# Steering_Wheel_Carrier_Board_Mezzanine.net
KiCad netlist of a schematic drawn in Altium Designer
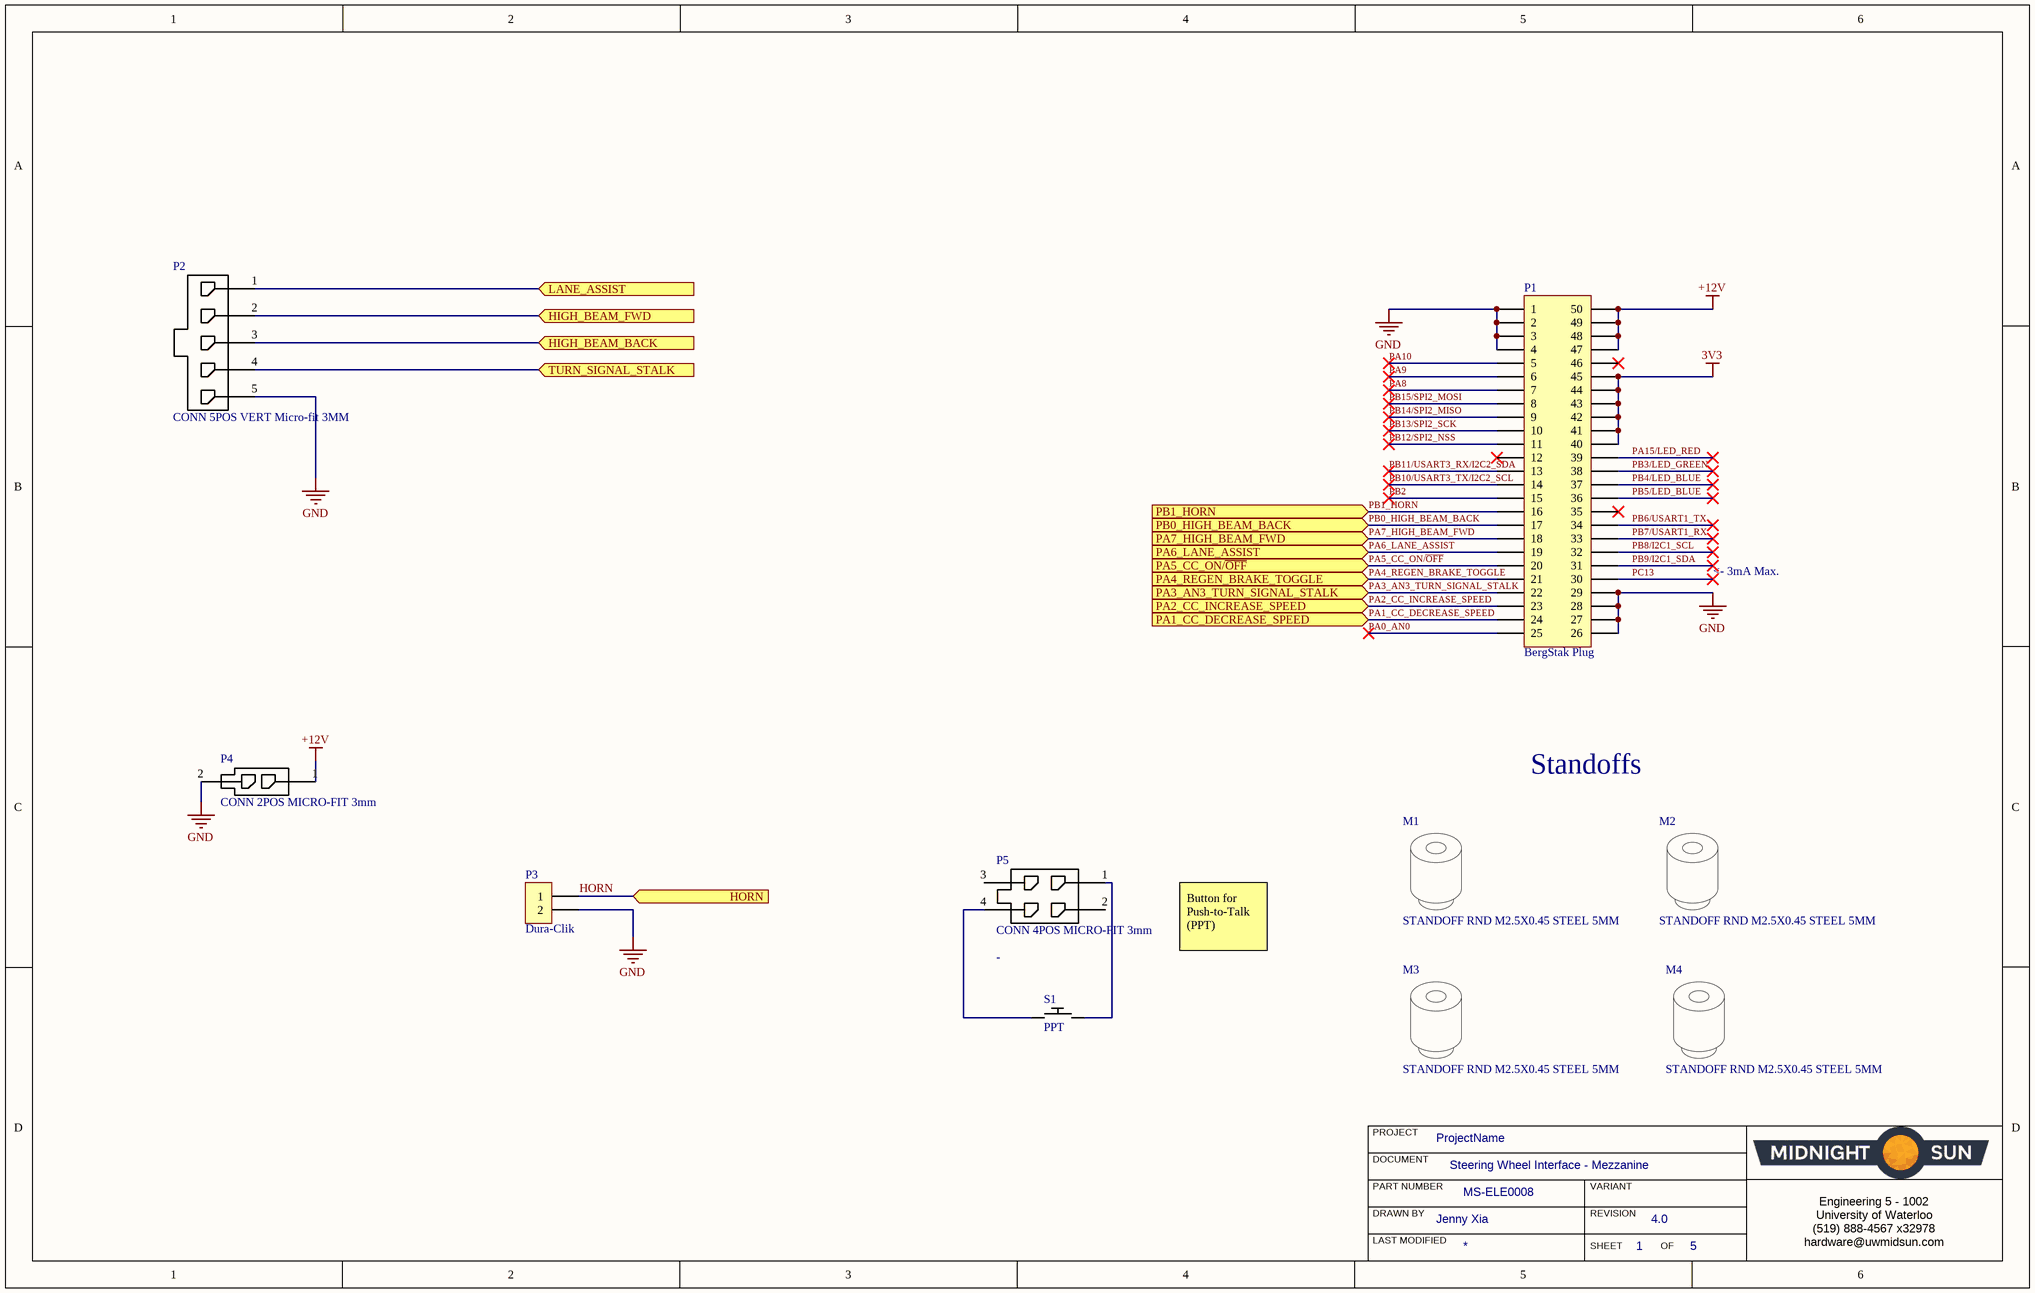
[diagram p0: Steering Wheel Carrier Board Mezzanine.SchDoc]

(export (version "E")
  (design (tool "Eeschema 10.0.6"))
  (components
    (comp (ref "M1")
      (value "STANDOFF RND M2.5X0.45 STEEL 5MM")
      (footprint "M2.5 Standoff")
      (fields
        (field (name "MANUFACTURER") "Wurth Electronics")
        (field (name "MANUFACTURER PART NUMBER") "9774050151R")
        (field (name "SOURCE") "Schematic Diagrams.SchLib")
      )
      (libsource (lib "University of Waterloo - Solar Car Team") (part "STANDOFF RND M2.5X0.45 STEEL 5MM"))
    )
    (comp (ref "M2")
      (value "STANDOFF RND M2.5X0.45 STEEL 5MM")
      (footprint "M2.5 Standoff")
      (fields
        (field (name "MANUFACTURER") "Wurth Electronics")
        (field (name "MANUFACTURER PART NUMBER") "9774050151R")
        (field (name "SOURCE") "Schematic Diagrams.SchLib")
      )
      (libsource (lib "University of Waterloo - Solar Car Team") (part "STANDOFF RND M2.5X0.45 STEEL 5MM"))
    )
    (comp (ref "M3")
      (value "STANDOFF RND M2.5X0.45 STEEL 5MM")
      (footprint "M2.5 Standoff")
      (fields
        (field (name "MANUFACTURER") "Wurth Electronics")
        (field (name "MANUFACTURER PART NUMBER") "9774050151R")
        (field (name "SOURCE") "Schematic Diagrams.SchLib")
      )
      (libsource (lib "University of Waterloo - Solar Car Team") (part "STANDOFF RND M2.5X0.45 STEEL 5MM"))
    )
    (comp (ref "M4")
      (value "STANDOFF RND M2.5X0.45 STEEL 5MM")
      (footprint "M2.5 Standoff")
      (fields
        (field (name "MANUFACTURER") "Wurth Electronics")
        (field (name "MANUFACTURER PART NUMBER") "9774050151R")
        (field (name "SOURCE") "Schematic Diagrams.SchLib")
      )
      (libsource (lib "University of Waterloo - Solar Car Team") (part "STANDOFF RND M2.5X0.45 STEEL 5MM"))
    )
    (comp (ref "P1")
      (value "CONN 50POS Bergstak Plug 0.02\"")
      (footprint "CONN, Bergstak 50 Pos Plug")
      (description "50 Position Connector Plug, Outer Shroud Contacts Surface Mount Gold")
      (fields (field (name "SERIES") "BergStak Plug"))
      (libsource (lib "Schematic Diagrams") (part "CONN 50POS Bergstak Plug 0.02{dblquote}"))
    )
    (comp (ref "P2")
      (value "CONN 5POS VERT Micro-fit 3MM")
      (footprint "CONN, 5POS MICRO-FIT 3mm")
      (description "Conn Power HDR 5 POS 3mm Solder ST Thru-Hole 5 Terminal 1 Port Micro-Fit 3.0™ Tray")
      (fields (field (name "MANUFACTURER PART NUMBER") "0436500516") (field (name "MANUFACTURER") "Molex"))
      (libsource (lib "University of Waterloo - Solar Car Team") (part "CONN 5POS VERT Micro-fit 3MM"))
    )
    (comp (ref "P3")
      (value "Dura-Clik")
      (footprint "CONN, 2POS Dura-Click Vertical")
      (description "2 Positions Header, Shrouded Connector 0.079\" (2.00mm) Surface Mount, Vertical Tin")
      (fields
        (field (name "MANUFACTURER") "Molex, LLC")
        (field (name "MANUFACTURER PART NUMBER") "5600200220")
      )
      (libsource (lib "Schematic Diagrams") (part "CONN 2POS DURA-CLIK 0.079{dblquote} VERT"))
    )
    (comp (ref "P4")
      (value "CONN 2POS MICRO-FIT 3mm")
      (footprint "CONN, 2POS MICRO-FIT")
      (description "Connector Header Through Hole 2 position")
      (fields
        (field (name "MANUFACTURER") "Molex")
        (field (name "MANUFACTURER PART NUMBER") "43045-0227")
        (field (name "SOURCE") "Schematic Diagrams.SchLib")
      )
      (libsource (lib "University of Waterloo - Solar Car Team") (part "CONN 2POS MICRO-FIT 3mm"))
    )
    (comp (ref "P5")
      (value "CONN 4POS MICRO-FIT 3mm")
      (footprint "CONN 4POS MICROFIT (2x2)")
      (fields
        (field (name "CURRENT RATING") "-")
        (field (name "MANUFACTURER") "Molex, LLC")
        (field (name "MANUFACTURER PART NUMBER") "430450427")
        (field (name "SOURCE") "Schematic Diagrams.SchLib")
      )
      (libsource (lib "University of Waterloo - Solar Car Team") (part "CONN 4POS MICRO-FIT 3mm"))
    )
    (comp (ref "S1")
      (value "PPT")
      (footprint "SW SPST-NO ESE-20C321")
      (description "Pushbutton Switch SPST-NO Standard Through Hole")
      (fields (field (name "MANUFACTURER") "Panasonic") (field (name "MANUFACTURER PART NUMBER") "ESE20C321"))
      (libsource (lib "Schematic Diagrams") (part "SW PUSH SPST-NO 0.1A 14V"))
    )
  )
  (nets
    (net (code "1") (name "+12V") (class "Default")
      (node (ref "P1") (pin "47") (pinfunction "47_47") (pintype "passive"))
      (node (ref "P1") (pin "48") (pinfunction "48_48") (pintype "passive"))
      (node (ref "P1") (pin "49") (pinfunction "49_49") (pintype "passive"))
      (node (ref "P1") (pin "50") (pinfunction "50_50") (pintype "passive"))
      (node (ref "P4") (pin "1") (pinfunction "1_1") (pintype "passive"))
    )
    (net (code "2") (name "/HIGH_BEAM_BACK") (class "Default")
      (node (ref "P2") (pin "3") (pinfunction "3_3") (pintype "passive"))
    )
    (net (code "3") (name "/HIGH_BEAM_FWD") (class "Default")
      (node (ref "P2") (pin "2") (pinfunction "2_2") (pintype "passive"))
    )
    (net (code "4") (name "/HORN") (class "Default")
      (node (ref "P3") (pin "1") (pinfunction "1_1") (pintype "passive"))
    )
    (net (code "5") (name "/LANE_ASSIST") (class "Default")
      (node (ref "P2") (pin "1") (pinfunction "1_1") (pintype "passive"))
    )
    (net (code "6") (name "/PA0_AN0") (class "Default")
      (node (ref "P1") (pin "25") (pinfunction "25_25") (pintype "passive+no_connect"))
    )
    (net (code "7") (name "/PA1_CC_DECREASE_SPEED") (class "Default")
      (node (ref "P1") (pin "24") (pinfunction "24_24") (pintype "passive"))
    )
    (net (code "8") (name "/PA2_CC_INCREASE_SPEED") (class "Default")
      (node (ref "P1") (pin "23") (pinfunction "23_23") (pintype "passive"))
    )
    (net (code "9") (name "/PA3_AN3_TURN_SIGNAL_STALK") (class "Default")
      (node (ref "P1") (pin "22") (pinfunction "22_22") (pintype "passive"))
    )
    (net (code "10") (name "/PA4_REGEN_BRAKE_TOGGLE") (class "Default")
      (node (ref "P1") (pin "21") (pinfunction "21_21") (pintype "passive"))
    )
    (net (code "11") (name "/PA5_CC_ON{slash}~{OFF}") (class "Default")
      (node (ref "P1") (pin "20") (pinfunction "20_20") (pintype "passive"))
    )
    (net (code "12") (name "/PA6_LANE_ASSIST") (class "Default")
      (node (ref "P1") (pin "19") (pinfunction "19_19") (pintype "passive"))
    )
    (net (code "13") (name "/PA7_HIGH_BEAM_FWD") (class "Default")
      (node (ref "P1") (pin "18") (pinfunction "18_18") (pintype "passive"))
    )
    (net (code "14") (name "/PA8") (class "Default")
      (node (ref "P1") (pin "7") (pinfunction "7_7") (pintype "passive+no_connect"))
    )
    (net (code "15") (name "/PA9") (class "Default")
      (node (ref "P1") (pin "6") (pinfunction "6_6") (pintype "passive+no_connect"))
    )
    (net (code "16") (name "/PA10") (class "Default")
      (node (ref "P1") (pin "5") (pinfunction "5_5") (pintype "passive+no_connect"))
    )
    (net (code "17") (name "/PA15{slash}LED_RED") (class "Default")
      (node (ref "P1") (pin "39") (pinfunction "39_39") (pintype "passive+no_connect"))
    )
    (net (code "18") (name "/PB0_HIGH_BEAM_BACK") (class "Default")
      (node (ref "P1") (pin "17") (pinfunction "17_17") (pintype "passive"))
    )
    (net (code "19") (name "/PB1_HORN") (class "Default")
      (node (ref "P1") (pin "16") (pinfunction "16_16") (pintype "passive"))
    )
    (net (code "20") (name "/PB2") (class "Default")
      (node (ref "P1") (pin "15") (pinfunction "15_15") (pintype "passive+no_connect"))
    )
    (net (code "21") (name "/PB3{slash}LED_GREEN") (class "Default")
      (node (ref "P1") (pin "38") (pinfunction "38_38") (pintype "passive+no_connect"))
    )
    (net (code "22") (name "/PB4{slash}LED_BLUE") (class "Default")
      (node (ref "P1") (pin "37") (pinfunction "37_37") (pintype "passive+no_connect"))
    )
    (net (code "23") (name "/PB5{slash}LED_BLUE") (class "Default")
      (node (ref "P1") (pin "36") (pinfunction "36_36") (pintype "passive+no_connect"))
    )
    (net (code "24") (name "/PB6{slash}USART1_TX") (class "Default")
      (node (ref "P1") (pin "34") (pinfunction "34_34") (pintype "passive+no_connect"))
    )
    (net (code "25") (name "/PB7{slash}USART1_RX") (class "Default")
      (node (ref "P1") (pin "33") (pinfunction "33_33") (pintype "passive+no_connect"))
    )
    (net (code "26") (name "/PB8{slash}I2C1_SCL") (class "Default")
      (node (ref "P1") (pin "32") (pinfunction "32_32") (pintype "passive+no_connect"))
    )
    (net (code "27") (name "/PB9{slash}I2C1_SDA") (class "Default")
      (node (ref "P1") (pin "31") (pinfunction "31_31") (pintype "passive+no_connect"))
    )
    (net (code "28") (name "/PB10{slash}USART3_TX{slash}I2C2_SCL") (class "Default")
      (node (ref "P1") (pin "14") (pinfunction "14_14") (pintype "passive+no_connect"))
    )
    (net (code "29") (name "/PB11{slash}USART3_RX{slash}I2C2_SDA") (class "Default")
      (node (ref "P1") (pin "13") (pinfunction "13_13") (pintype "passive+no_connect"))
    )
    (net (code "30") (name "/PB12{slash}SPI2_NSS") (class "Default")
      (node (ref "P1") (pin "11") (pinfunction "11_11") (pintype "passive+no_connect"))
    )
    (net (code "31") (name "/PB13{slash}SPI2_SCK") (class "Default")
      (node (ref "P1") (pin "10") (pinfunction "10_10") (pintype "passive+no_connect"))
    )
    (net (code "32") (name "/PB14{slash}SPI2_MISO") (class "Default")
      (node (ref "P1") (pin "9") (pinfunction "9_9") (pintype "passive+no_connect"))
    )
    (net (code "33") (name "/PB15{slash}SPI2_MOSI") (class "Default")
      (node (ref "P1") (pin "8") (pinfunction "8_8") (pintype "passive+no_connect"))
    )
    (net (code "34") (name "/PC13") (class "Default")
      (node (ref "P1") (pin "30") (pinfunction "30_30") (pintype "passive+no_connect"))
    )
    (net (code "35") (name "/TURN_SIGNAL_STALK") (class "Default")
      (node (ref "P2") (pin "4") (pinfunction "4_4") (pintype "passive"))
    )
    (net (code "36") (name "3V3") (class "Default")
      (node (ref "P1") (pin "40") (pinfunction "40_40") (pintype "passive"))
      (node (ref "P1") (pin "41") (pinfunction "41_41") (pintype "passive"))
      (node (ref "P1") (pin "42") (pinfunction "42_42") (pintype "passive"))
      (node (ref "P1") (pin "43") (pinfunction "43_43") (pintype "passive"))
      (node (ref "P1") (pin "44") (pinfunction "44_44") (pintype "passive"))
      (node (ref "P1") (pin "45") (pinfunction "45_45") (pintype "passive"))
    )
    (net (code "37") (name "GND") (class "Default")
      (node (ref "P1") (pin "1") (pinfunction "1_1") (pintype "passive"))
      (node (ref "P1") (pin "2") (pinfunction "2_2") (pintype "passive"))
      (node (ref "P1") (pin "26") (pinfunction "26_26") (pintype "passive"))
      (node (ref "P1") (pin "27") (pinfunction "27_27") (pintype "passive"))
      (node (ref "P1") (pin "28") (pinfunction "28_28") (pintype "passive"))
      (node (ref "P1") (pin "29") (pinfunction "29_29") (pintype "passive"))
      (node (ref "P1") (pin "3") (pinfunction "3_3") (pintype "passive"))
      (node (ref "P1") (pin "4") (pinfunction "4_4") (pintype "passive"))
      (node (ref "P2") (pin "5") (pinfunction "5_5") (pintype "passive"))
      (node (ref "P3") (pin "2") (pinfunction "2_2") (pintype "passive"))
      (node (ref "P4") (pin "2") (pinfunction "2_2") (pintype "passive"))
    )
    (net (code "38") (name "Net-(P5-Pad1)") (class "Default")
      (node (ref "P5") (pin "1") (pinfunction "1_1") (pintype "passive"))
      (node (ref "S1") (pin "2") (pinfunction "2_2") (pintype "passive"))
    )
    (net (code "39") (name "Net-(P5-Pad4)") (class "Default")
      (node (ref "P5") (pin "4") (pinfunction "4_4") (pintype "passive"))
      (node (ref "S1") (pin "1") (pinfunction "1_1") (pintype "passive"))
    )
    (net (code "40") (name "unconnected-(P1-Pad12)") (class "Default")
      (node (ref "P1") (pin "12") (pinfunction "12_12") (pintype "passive+no_connect"))
    )
    (net (code "41") (name "unconnected-(P1-Pad35)") (class "Default")
      (node (ref "P1") (pin "35") (pinfunction "35_35") (pintype "passive+no_connect"))
    )
    (net (code "42") (name "unconnected-(P1-Pad46)") (class "Default")
      (node (ref "P1") (pin "46") (pinfunction "46_46") (pintype "passive+no_connect"))
    )
    (net (code "43") (name "unconnected-(P5-Pad2)") (class "Default")
      (node (ref "P5") (pin "2") (pinfunction "2_2") (pintype "passive"))
    )
    (net (code "44") (name "unconnected-(P5-Pad3)") (class "Default")
      (node (ref "P5") (pin "3") (pinfunction "3_3") (pintype "passive"))
    )
  )
)
